# Sheet1.net
KiCad netlist of a schematic drawn in Altium Designer
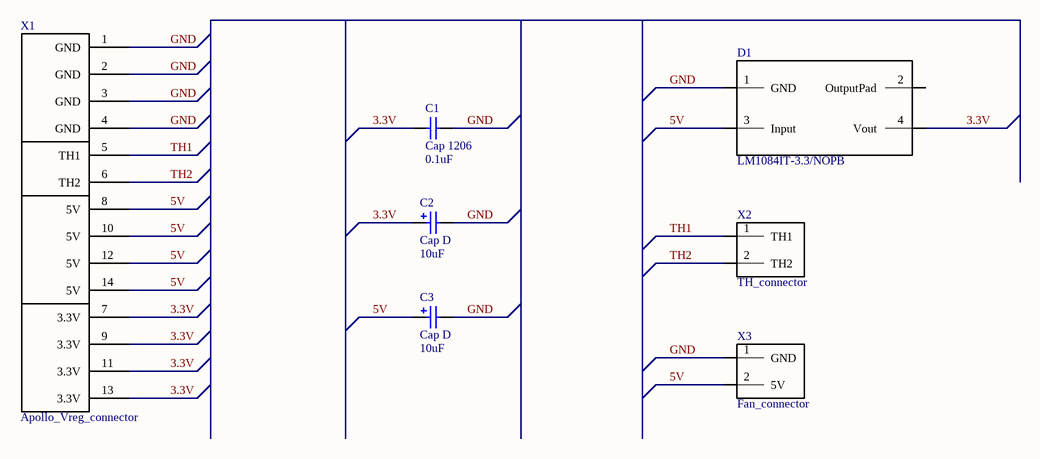
[diagram p0: Sheet1.SchDoc]

(export (version "E")
  (design (tool "Eeschema 10.0.6"))
  (components
    (comp (ref "C1")
      (value "Cap 1206")
      (footprint "C1206")
      (description "Capacitor (Semiconductor SIM Model)")
      (fields (field (name "ALTIUM_VALUE") "0.1uF") (field (name "PUBLISHER") "Altium Limited"))
      (libsource (lib "Vreg") (part "Cap 1206"))
    )
    (comp (ref "C2")
      (value "Cap D")
      (footprint "CAPCP3825X06N")
      (description "Polarized Capacitor (Surface Mount)")
      (fields (field (name "ALTIUM_VALUE") "10uF") (field (name "PUBLISHER") "Altium Limited"))
      (libsource (lib "Vreg") (part "Cap D"))
    )
    (comp (ref "C3")
      (value "Cap D")
      (footprint "CAPCP3825X06N")
      (description "Polarized Capacitor (Surface Mount)")
      (fields (field (name "ALTIUM_VALUE") "10uF") (field (name "PUBLISHER") "Altium Limited"))
      (libsource (lib "Vreg") (part "Cap D"))
    )
    (comp (ref "D1")
      (value "LM1084IT-3.3/NOPB")
      (footprint "TO220HS")
      (libsource (lib "Vreg") (part "LM1084IT-3.3/NOPB"))
    )
    (comp (ref "X1")
      (value "Apollo_Vreg_connector")
      (footprint "Apollo_Vreg_connector")
      (libsource (lib "Vreg") (part "Apollo_Vreg_connector"))
    )
    (comp (ref "X2")
      (value "TH_connector")
      (footprint "HDR1X2")
      (libsource (lib "Vreg") (part "TH_connector"))
    )
    (comp (ref "X3")
      (value "Fan_connector")
      (footprint "HDR1X2")
      (libsource (lib "Vreg") (part "Fan_connector"))
    )
  )
  (nets
    (net (code "1") (name "/3.3V") (class "Default")
      (node (ref "C1") (pin "1") (pinfunction "1_1") (pintype "passive"))
      (node (ref "C2") (pin "1") (pinfunction "1_1") (pintype "passive"))
      (node (ref "D1") (pin "4") (pinfunction "Vout_4") (pintype "passive"))
      (node (ref "X1") (pin "11") (pinfunction "3.3V_11") (pintype "passive"))
      (node (ref "X1") (pin "13") (pinfunction "3.3V_13") (pintype "passive"))
      (node (ref "X1") (pin "7") (pinfunction "3.3V_7") (pintype "passive"))
      (node (ref "X1") (pin "9") (pinfunction "3.3V_9") (pintype "passive"))
    )
    (net (code "2") (name "/5V") (class "Default")
      (node (ref "C3") (pin "1") (pinfunction "1_1") (pintype "passive"))
      (node (ref "D1") (pin "3") (pinfunction "Input_3") (pintype "passive"))
      (node (ref "X1") (pin "10") (pinfunction "5V_10") (pintype "passive"))
      (node (ref "X1") (pin "12") (pinfunction "5V_12") (pintype "passive"))
      (node (ref "X1") (pin "14") (pinfunction "5V_14") (pintype "passive"))
      (node (ref "X1") (pin "8") (pinfunction "5V_8") (pintype "passive"))
      (node (ref "X3") (pin "2") (pinfunction "5V_2") (pintype "passive"))
    )
    (net (code "3") (name "/GND") (class "Default")
      (node (ref "C1") (pin "2") (pinfunction "2_2") (pintype "passive"))
      (node (ref "C2") (pin "2") (pinfunction "2_2") (pintype "passive"))
      (node (ref "C3") (pin "2") (pinfunction "2_2") (pintype "passive"))
      (node (ref "D1") (pin "1") (pinfunction "GND_1") (pintype "passive"))
      (node (ref "X1") (pin "1") (pinfunction "GND_1") (pintype "passive"))
      (node (ref "X1") (pin "2") (pinfunction "GND_2") (pintype "passive"))
      (node (ref "X1") (pin "3") (pinfunction "GND_3") (pintype "passive"))
      (node (ref "X1") (pin "4") (pinfunction "GND_4") (pintype "passive"))
      (node (ref "X3") (pin "1") (pinfunction "GND_1") (pintype "passive"))
    )
    (net (code "4") (name "/TH1") (class "Default")
      (node (ref "X1") (pin "5") (pinfunction "TH1_5") (pintype "passive"))
      (node (ref "X2") (pin "1") (pinfunction "TH1_1") (pintype "passive"))
    )
    (net (code "5") (name "/TH2") (class "Default")
      (node (ref "X1") (pin "6") (pinfunction "TH2_6") (pintype "passive"))
      (node (ref "X2") (pin "2") (pinfunction "TH2_2") (pintype "passive"))
    )
    (net (code "6") (name "unconnected-(D1-OutputPad-Pad2)") (class "Default")
      (node (ref "D1") (pin "2") (pinfunction "OutputPad_2") (pintype "passive"))
    )
  )
)
